# New_Project.net
KiCad netlist of a schematic drawn in EasyEDA Pro
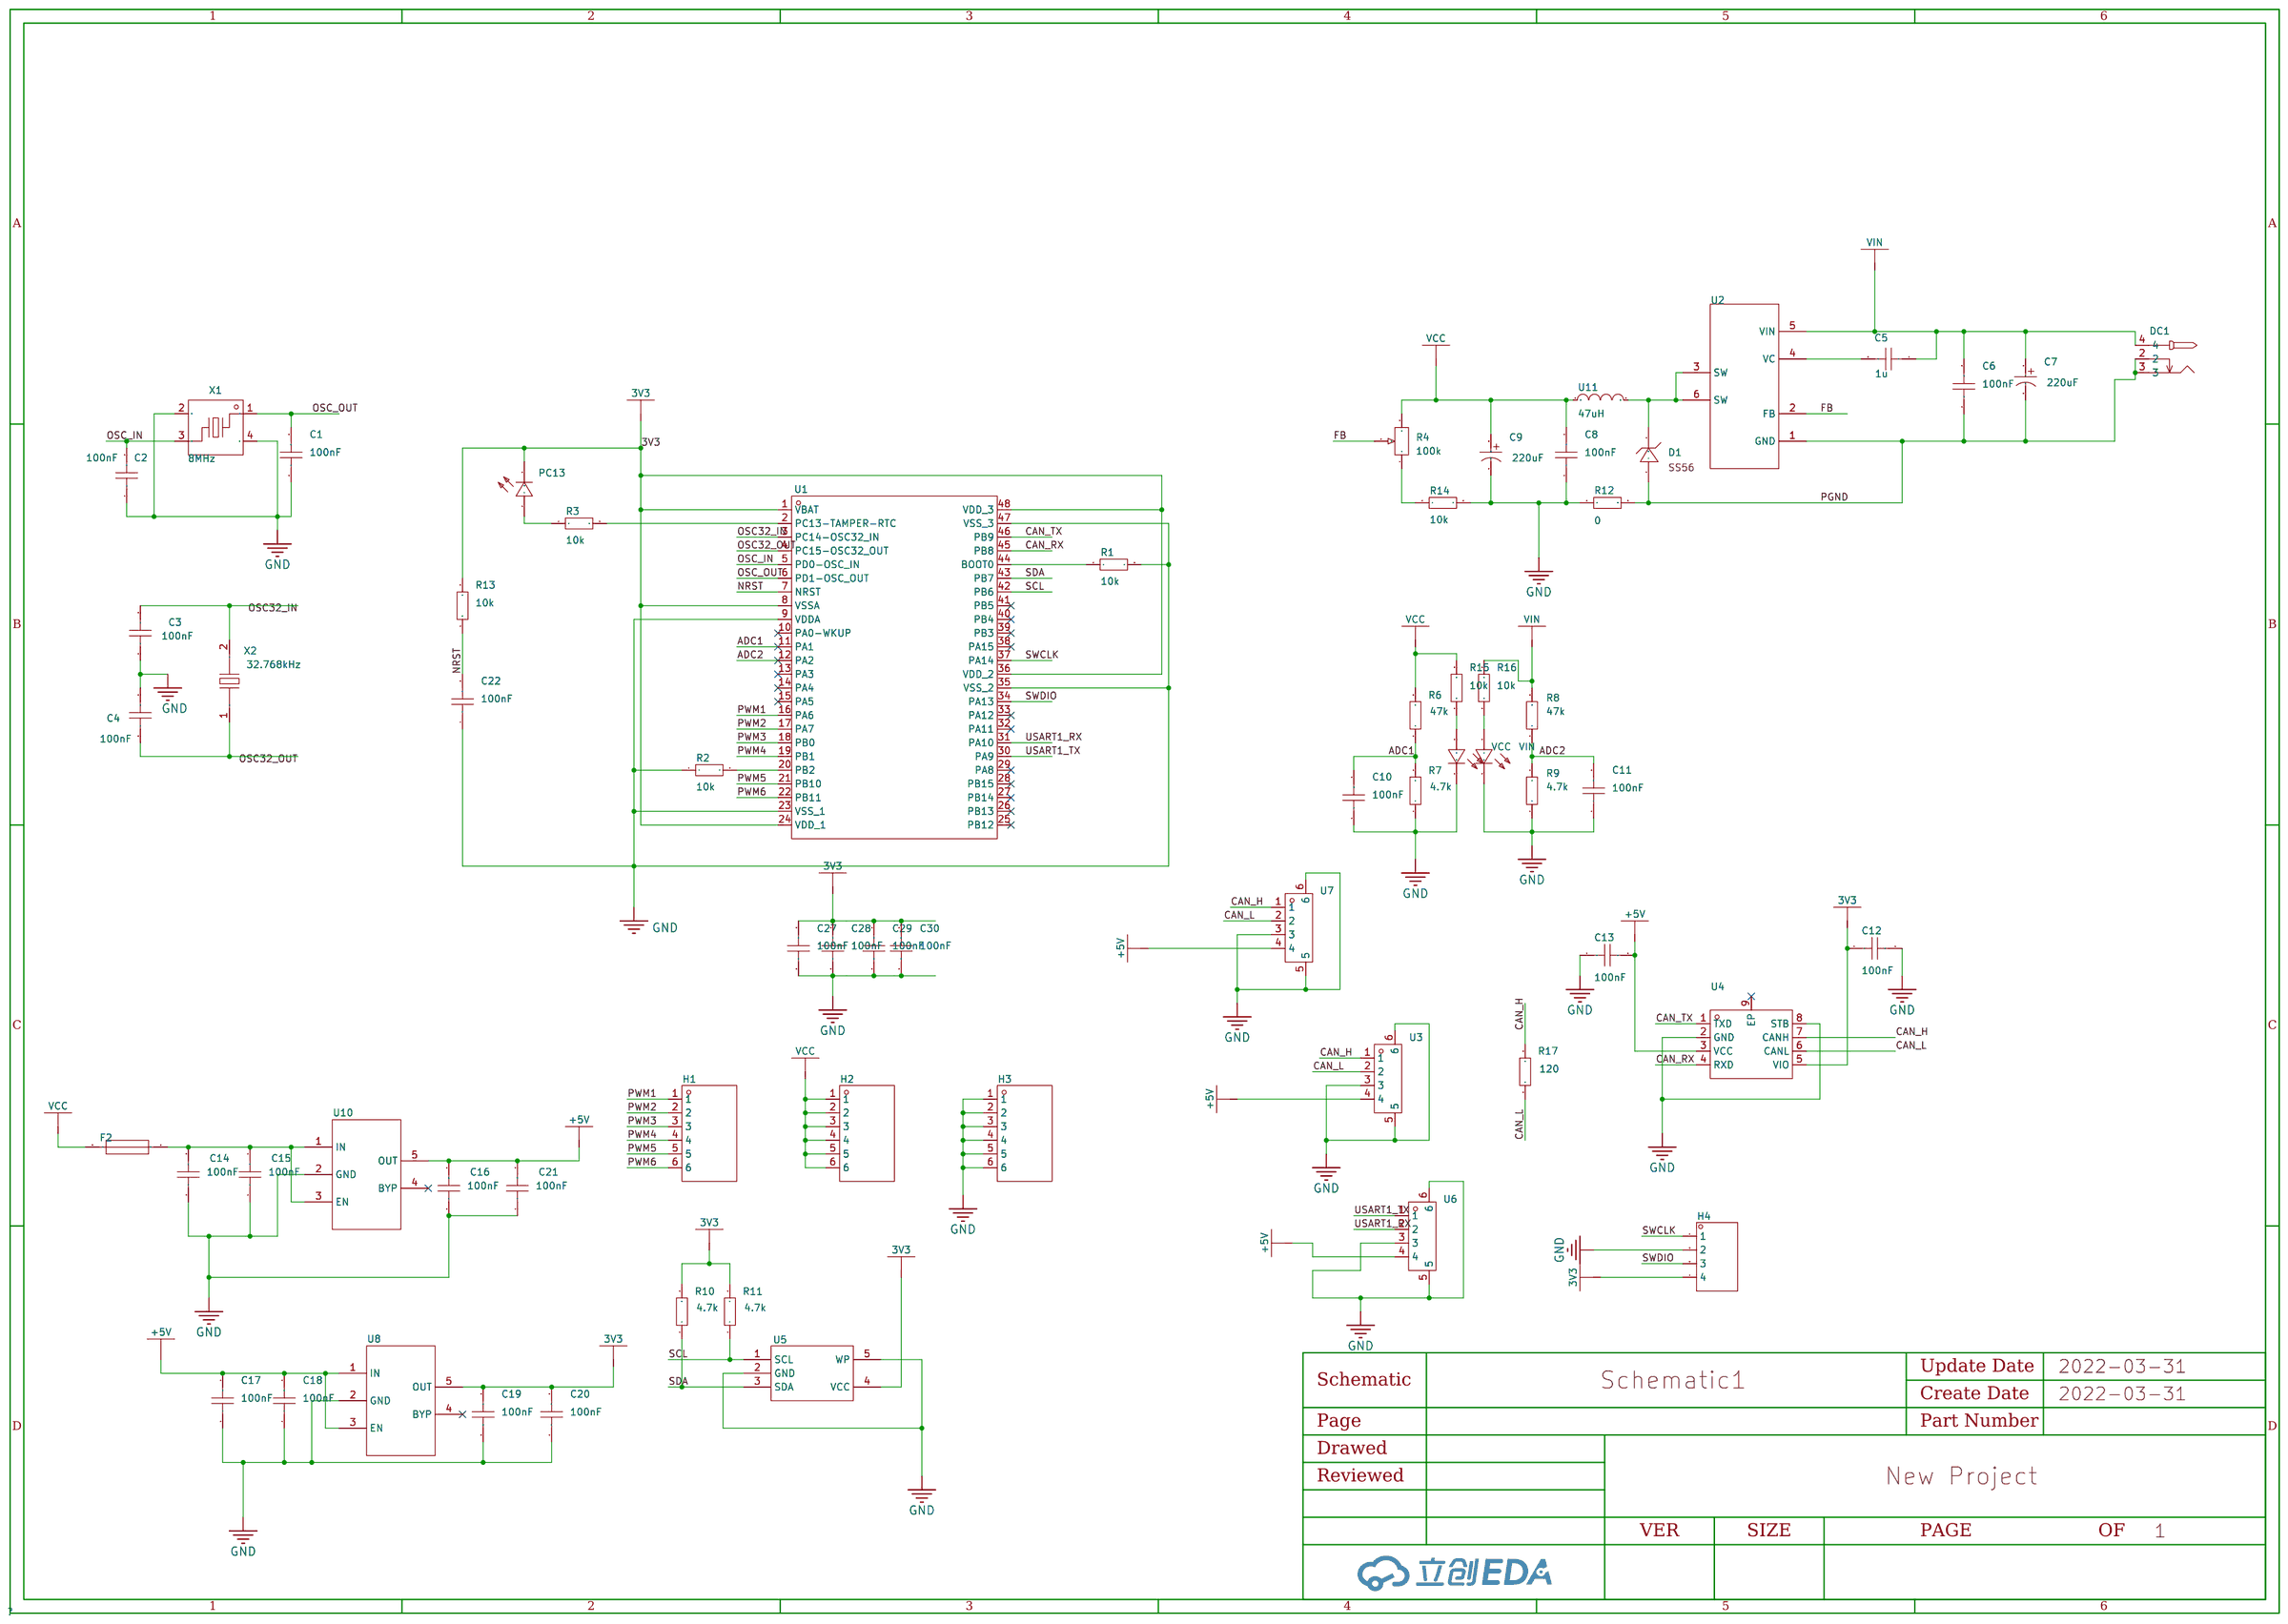
[diagram p0: schematic sheet]

(export (version "E")
  (design (tool "Eeschema 10.0.6"))
  (components
    (comp (ref "C1")
      (value "100nF")
      (footprint "easyedapro:C0603")
      (description "容值:100nF;精度:±10%;额定电压:50V;温度系数:X7R;")
      (fields
        (field (name "Manufacturer Part") "CC0603KRX7R9BB104")
        (field (name "Manufacturer") "YAGEO(国巨)")
      )
      (libsource (lib "easyedapro") (part "CC0603KRX7R9BB104"))
    )
    (comp (ref "C2")
      (value "100nF")
      (footprint "easyedapro:C0603")
      (description "容值:100nF;精度:±10%;额定电压:50V;温度系数:X7R;")
      (fields
        (field (name "Manufacturer Part") "CC0603KRX7R9BB104")
        (field (name "Manufacturer") "YAGEO(国巨)")
      )
      (libsource (lib "easyedapro") (part "CC0603KRX7R9BB104"))
    )
    (comp (ref "C3")
      (value "100nF")
      (footprint "easyedapro:C0603")
      (description "容值:100nF;精度:±10%;额定电压:50V;温度系数:X7R;")
      (fields
        (field (name "Manufacturer Part") "CC0603KRX7R9BB104")
        (field (name "Manufacturer") "YAGEO(国巨)")
      )
      (libsource (lib "easyedapro") (part "CC0603KRX7R9BB104"))
    )
    (comp (ref "C4")
      (value "100nF")
      (footprint "easyedapro:C0603")
      (description "容值:100nF;精度:±10%;额定电压:50V;温度系数:X7R;")
      (fields
        (field (name "Manufacturer Part") "CC0603KRX7R9BB104")
        (field (name "Manufacturer") "YAGEO(国巨)")
      )
      (libsource (lib "easyedapro") (part "CC0603KRX7R9BB104"))
    )
    (comp (ref "C5")
      (value "1u")
      (footprint "easyedapro:C0603")
      (description "容值:100nF;精度:±10%;额定电压:50V;温度系数:X7R;")
      (fields
        (field (name "Manufacturer Part") "CC0603KRX7R9BB104")
        (field (name "Manufacturer") "YAGEO(国巨)")
      )
      (libsource (lib "easyedapro") (part "CC0603KRX7R9BB104"))
    )
    (comp (ref "C6")
      (value "100nF")
      (footprint "easyedapro:C0603")
      (description "容值:100nF;精度:±10%;额定电压:50V;温度系数:X7R;")
      (fields
        (field (name "Manufacturer Part") "CC0603KRX7R9BB104")
        (field (name "Manufacturer") "YAGEO(国巨)")
      )
      (libsource (lib "easyedapro") (part "CC0603KRX7R9BB104"))
    )
    (comp (ref "C7")
      (value "220uF")
      (footprint "easyedapro:CAP-SMD_BD6.3-L6.6-W6.6-FD-1")
      (description "容值:10uF;精度:±20%;额定电压:50V;电容体直径:6.3mm;电容体长度:5.5mm;纹波电流:-;等效串联电阻:-;工作寿命:2000hrs@85;工作温度:-40~+85;")
      (fields
        (field (name "Manufacturer Part") "50SEV10M6.3X5.5")
        (field (name "Manufacturer") "rubycon(红宝石)")
      )
      (libsource (lib "easyedapro") (part "50SEV10M6.3X5.5"))
    )
    (comp (ref "C8")
      (value "100nF")
      (footprint "easyedapro:C0603")
      (description "容值:100nF;精度:±10%;额定电压:50V;温度系数:X7R;")
      (fields
        (field (name "Manufacturer Part") "CC0603KRX7R9BB104")
        (field (name "Manufacturer") "YAGEO(国巨)")
      )
      (libsource (lib "easyedapro") (part "CC0603KRX7R9BB104"))
    )
    (comp (ref "C9")
      (value "220uF")
      (footprint "easyedapro:CAP-SMD_BD6.3-L6.6-W6.6-FD-1")
      (description "容值:10uF;精度:±20%;额定电压:50V;电容体直径:6.3mm;电容体长度:5.5mm;纹波电流:-;等效串联电阻:-;工作寿命:2000hrs@85;工作温度:-40~+85;")
      (fields
        (field (name "Manufacturer Part") "50SEV10M6.3X5.5")
        (field (name "Manufacturer") "rubycon(红宝石)")
      )
      (libsource (lib "easyedapro") (part "50SEV10M6.3X5.5"))
    )
    (comp (ref "C10")
      (value "100nF")
      (footprint "easyedapro:C0603")
      (description "容值:100nF;精度:±10%;额定电压:50V;温度系数:X7R;")
      (fields
        (field (name "Manufacturer Part") "CC0603KRX7R9BB104")
        (field (name "Manufacturer") "YAGEO(国巨)")
      )
      (libsource (lib "easyedapro") (part "CC0603KRX7R9BB104"))
    )
    (comp (ref "C11")
      (value "100nF")
      (footprint "easyedapro:C0603")
      (description "容值:100nF;精度:±10%;额定电压:50V;温度系数:X7R;")
      (fields
        (field (name "Manufacturer Part") "CC0603KRX7R9BB104")
        (field (name "Manufacturer") "YAGEO(国巨)")
      )
      (libsource (lib "easyedapro") (part "CC0603KRX7R9BB104"))
    )
    (comp (ref "C12")
      (value "100nF")
      (footprint "easyedapro:C0603")
      (description "容值:100nF;精度:±10%;额定电压:50V;温度系数:X7R;")
      (fields
        (field (name "Manufacturer Part") "CC0603KRX7R9BB104")
        (field (name "Manufacturer") "YAGEO(国巨)")
      )
      (libsource (lib "easyedapro") (part "CC0603KRX7R9BB104"))
    )
    (comp (ref "C13")
      (value "100nF")
      (footprint "easyedapro:C0603")
      (description "容值:100nF;精度:±10%;额定电压:50V;温度系数:X7R;")
      (fields
        (field (name "Manufacturer Part") "CC0603KRX7R9BB104")
        (field (name "Manufacturer") "YAGEO(国巨)")
      )
      (libsource (lib "easyedapro") (part "CC0603KRX7R9BB104"))
    )
    (comp (ref "C14")
      (value "100nF")
      (footprint "easyedapro:C0603")
      (description "容值:100nF;精度:±10%;额定电压:50V;温度系数:X7R;")
      (fields
        (field (name "Manufacturer Part") "CC0603KRX7R9BB104")
        (field (name "Manufacturer") "YAGEO(国巨)")
      )
      (libsource (lib "easyedapro") (part "CC0603KRX7R9BB104"))
    )
    (comp (ref "C15")
      (value "100nF")
      (footprint "easyedapro:C0603")
      (description "容值:100nF;精度:±10%;额定电压:50V;温度系数:X7R;")
      (fields
        (field (name "Manufacturer Part") "CC0603KRX7R9BB104")
        (field (name "Manufacturer") "YAGEO(国巨)")
      )
      (libsource (lib "easyedapro") (part "CC0603KRX7R9BB104"))
    )
    (comp (ref "C16")
      (value "100nF")
      (footprint "easyedapro:C0603")
      (description "容值:100nF;精度:±10%;额定电压:50V;温度系数:X7R;")
      (fields
        (field (name "Manufacturer Part") "CC0603KRX7R9BB104")
        (field (name "Manufacturer") "YAGEO(国巨)")
      )
      (libsource (lib "easyedapro") (part "CC0603KRX7R9BB104"))
    )
    (comp (ref "C17")
      (value "100nF")
      (footprint "easyedapro:C0603")
      (description "容值:100nF;精度:±10%;额定电压:50V;温度系数:X7R;")
      (fields
        (field (name "Manufacturer Part") "CC0603KRX7R9BB104")
        (field (name "Manufacturer") "YAGEO(国巨)")
      )
      (libsource (lib "easyedapro") (part "CC0603KRX7R9BB104"))
    )
    (comp (ref "C18")
      (value "100nF")
      (footprint "easyedapro:C0603")
      (description "容值:100nF;精度:±10%;额定电压:50V;温度系数:X7R;")
      (fields
        (field (name "Manufacturer Part") "CC0603KRX7R9BB104")
        (field (name "Manufacturer") "YAGEO(国巨)")
      )
      (libsource (lib "easyedapro") (part "CC0603KRX7R9BB104"))
    )
    (comp (ref "C19")
      (value "100nF")
      (footprint "easyedapro:C0603")
      (description "容值:100nF;精度:±10%;额定电压:50V;温度系数:X7R;")
      (fields
        (field (name "Manufacturer Part") "CC0603KRX7R9BB104")
        (field (name "Manufacturer") "YAGEO(国巨)")
      )
      (libsource (lib "easyedapro") (part "CC0603KRX7R9BB104"))
    )
    (comp (ref "C20")
      (value "100nF")
      (footprint "easyedapro:C0603")
      (description "容值:100nF;精度:±10%;额定电压:50V;温度系数:X7R;")
      (fields
        (field (name "Manufacturer Part") "CC0603KRX7R9BB104")
        (field (name "Manufacturer") "YAGEO(国巨)")
      )
      (libsource (lib "easyedapro") (part "CC0603KRX7R9BB104"))
    )
    (comp (ref "C21")
      (value "100nF")
      (footprint "easyedapro:C0603")
      (description "容值:100nF;精度:±10%;额定电压:50V;温度系数:X7R;")
      (fields
        (field (name "Manufacturer Part") "CC0603KRX7R9BB104")
        (field (name "Manufacturer") "YAGEO(国巨)")
      )
      (libsource (lib "easyedapro") (part "CC0603KRX7R9BB104"))
    )
    (comp (ref "C22")
      (value "100nF")
      (footprint "easyedapro:C0603")
      (description "容值:100nF;精度:±10%;额定电压:50V;温度系数:X7R;")
      (fields
        (field (name "Manufacturer Part") "CC0603KRX7R9BB104")
        (field (name "Manufacturer") "YAGEO(国巨)")
      )
      (libsource (lib "easyedapro") (part "CC0603KRX7R9BB104"))
    )
    (comp (ref "C27")
      (value "100nF")
      (footprint "easyedapro:C0603")
      (description "容值:100nF;精度:±10%;额定电压:50V;温度系数:X7R;")
      (fields
        (field (name "Manufacturer Part") "CC0603KRX7R9BB104")
        (field (name "Manufacturer") "YAGEO(国巨)")
      )
      (libsource (lib "easyedapro") (part "CC0603KRX7R9BB104"))
    )
    (comp (ref "C28")
      (value "100nF")
      (footprint "easyedapro:C0603")
      (description "容值:100nF;精度:±10%;额定电压:50V;温度系数:X7R;")
      (fields
        (field (name "Manufacturer Part") "CC0603KRX7R9BB104")
        (field (name "Manufacturer") "YAGEO(国巨)")
      )
      (libsource (lib "easyedapro") (part "CC0603KRX7R9BB104"))
    )
    (comp (ref "C29")
      (value "100nF")
      (footprint "easyedapro:C0603")
      (description "容值:100nF;精度:±10%;额定电压:50V;温度系数:X7R;")
      (fields
        (field (name "Manufacturer Part") "CC0603KRX7R9BB104")
        (field (name "Manufacturer") "YAGEO(国巨)")
      )
      (libsource (lib "easyedapro") (part "CC0603KRX7R9BB104"))
    )
    (comp (ref "C30")
      (value "100nF")
      (footprint "easyedapro:C0603")
      (description "容值:100nF;精度:±10%;额定电压:50V;温度系数:X7R;")
      (fields
        (field (name "Manufacturer Part") "CC0603KRX7R9BB104")
        (field (name "Manufacturer") "YAGEO(国巨)")
      )
      (libsource (lib "easyedapro") (part "CC0603KRX7R9BB104"))
    )
    (comp (ref "D1")
      (value "~")
      (footprint "easyedapro:SMA_L4.4-W2.6-LS5.0-RD")
      (description "直流反向耐压（Vr）:60V;平均整流电流（Io）:5A;正向压降（Vf）:550mV @ 5A;")
      (fields (field (name "Manufacturer Part") "SS56") (field (name "LCSC Part Name") "SS56"))
      (libsource (lib "easyedapro") (part "SS56_C379835"))
    )
    (comp (ref "DC1")
      (value "~")
      (footprint "easyedapro:DC-IN-TH_DC-5520-1")
      (description "连接器类型:DC电源插座;安装方式:弯插;触点内径:2mm;触点外径:6.4mm;额定电流:-;额定电压:-;工作温度范围:-;")
      (fields (field (name "Manufacturer Part") "DC-005 2.0") (field (name "Manufacturer") "BOOMELE(博穆精密)"))
      (libsource (lib "easyedapro") (part "DC-005 5.5-2.0MM"))
    )
    (comp (ref "F2")
      (value "~")
      (footprint "easyedapro:F1206")
      (fields (field (name "Manufacturer Part") "JK-nSMD050-30") (field (name "Manufacturer") "JK(金科)"))
      (libsource (lib "easyedapro") (part "JK-NSMD050-30V"))
    )
    (comp (ref "H1")
      (value "~")
      (footprint "easyedapro:HDR-TH_6P-P2.54-V_Z-211-0611-0021-001")
      (fields
        (field (name "Manufacturer Part") "Z-211-0611-0021-001")
        (field (name "Manufacturer") "Nextron(台湾正凌)")
      )
      (libsource (lib "easyedapro") (part "Z-211-0611-0021-001"))
    )
    (comp (ref "H2")
      (value "~")
      (footprint "easyedapro:HDR-TH_6P-P2.54-V_Z-211-0611-0021-001")
      (fields
        (field (name "Manufacturer Part") "Z-211-0611-0021-001")
        (field (name "Manufacturer") "Nextron(台湾正凌)")
      )
      (libsource (lib "easyedapro") (part "Z-211-0611-0021-001"))
    )
    (comp (ref "H3")
      (value "~")
      (footprint "easyedapro:HDR-TH_6P-P2.54-V_Z-211-0611-0021-001")
      (fields
        (field (name "Manufacturer Part") "Z-211-0611-0021-001")
        (field (name "Manufacturer") "Nextron(台湾正凌)")
      )
      (libsource (lib "easyedapro") (part "Z-211-0611-0021-001"))
    )
    (comp (ref "H4")
      (value "~")
      (footprint "easyedapro:HDR-TH_4P-P2.54-V-M")
      (fields (field (name "Manufacturer Part") "B-2100S04P-A110") (field (name "Manufacturer") "Ckmtw(灿科盟)"))
      (libsource (lib "easyedapro") (part "Header-Male-2.54_1x4"))
    )
    (comp (ref "PC13")
      (value "~")
      (footprint "easyedapro:LED0603-R-RD")
      (fields
        (field (name "Manufacturer Part") "19-217/GHC-YR1S2/3T")
        (field (name "Manufacturer") "EVERLIGHT(台湾亿光)")
      )
      (libsource (lib "easyedapro") (part "19-217/GHC-YR1S2/3T"))
    )
    (comp (ref "R1")
      (value "10k")
      (footprint "easyedapro:R0201")
      (description "阻值:10k;精度:±1%;功率:50mW;温度系数:±200ppm/;最大工作电压:25V;工作温度范围:-55~+125;")
      (fields (field (name "Manufacturer Part") "RC-01W1002FT") (field (name "Manufacturer") "FH(风华)"))
      (libsource (lib "easyedapro") (part "RC-01W1002FT"))
    )
    (comp (ref "R2")
      (value "10k")
      (footprint "easyedapro:R0201")
      (description "阻值:10k;精度:±1%;功率:50mW;温度系数:±200ppm/;最大工作电压:25V;工作温度范围:-55~+125;")
      (fields (field (name "Manufacturer Part") "RC-01W1002FT") (field (name "Manufacturer") "FH(风华)"))
      (libsource (lib "easyedapro") (part "RC-01W1002FT"))
    )
    (comp (ref "R3")
      (value "10k")
      (footprint "easyedapro:R0201")
      (description "阻值:10k;精度:±1%;功率:50mW;温度系数:±200ppm/;最大工作电压:25V;工作温度范围:-55~+125;")
      (fields (field (name "Manufacturer Part") "RC-01W1002FT") (field (name "Manufacturer") "FH(风华)"))
      (libsource (lib "easyedapro") (part "RC-01W1002FT"))
    )
    (comp (ref "R4")
      (value "100k")
      (footprint "easyedapro:RES-ADJ-TH_3P-L9.5-W4.9-P2.50-L_3296W")
      (description "阻值:100k;精度:±10%;温度系数:±250ppm/;")
      (fields (field (name "Manufacturer Part") "3296W-1-104") (field (name "Manufacturer") "BOCHEN(博晨)"))
      (libsource (lib "easyedapro") (part "3296W-1-104"))
    )
    (comp (ref "R6")
      (value "47k")
      (footprint "easyedapro:R0201")
      (description "阻值:10k;精度:±1%;功率:50mW;温度系数:±200ppm/;最大工作电压:25V;工作温度范围:-55~+125;")
      (fields (field (name "Manufacturer Part") "RC-01W1002FT") (field (name "Manufacturer") "FH(风华)"))
      (libsource (lib "easyedapro") (part "RC-01W1002FT"))
    )
    (comp (ref "R7")
      (value "4.7k")
      (footprint "easyedapro:R0201")
      (description "阻值:10k;精度:±1%;功率:50mW;温度系数:±200ppm/;最大工作电压:25V;工作温度范围:-55~+125;")
      (fields (field (name "Manufacturer Part") "RC-01W1002FT") (field (name "Manufacturer") "FH(风华)"))
      (libsource (lib "easyedapro") (part "RC-01W1002FT"))
    )
    (comp (ref "R8")
      (value "47k")
      (footprint "easyedapro:R0201")
      (description "阻值:10k;精度:±1%;功率:50mW;温度系数:±200ppm/;最大工作电压:25V;工作温度范围:-55~+125;")
      (fields (field (name "Manufacturer Part") "RC-01W1002FT") (field (name "Manufacturer") "FH(风华)"))
      (libsource (lib "easyedapro") (part "RC-01W1002FT"))
    )
    (comp (ref "R9")
      (value "4.7k")
      (footprint "easyedapro:R0201")
      (description "阻值:10k;精度:±1%;功率:50mW;温度系数:±200ppm/;最大工作电压:25V;工作温度范围:-55~+125;")
      (fields (field (name "Manufacturer Part") "RC-01W1002FT") (field (name "Manufacturer") "FH(风华)"))
      (libsource (lib "easyedapro") (part "RC-01W1002FT"))
    )
    (comp (ref "R10")
      (value "4.7k")
      (footprint "easyedapro:R0603")
      (description "电阻类型:薄膜电阻;阻值:10k;精度:±0.1%;功率:100mW;温度系数:±25ppm/;最大工作电压:75V;工作温度范围:-55~+155;")
      (fields
        (field (name "Manufacturer Part") "TR0603B10K0P0525Z")
        (field (name "Manufacturer") "EVER OHMS(天二科技)")
      )
      (libsource (lib "easyedapro") (part "TR0603B10KP05250.1W"))
    )
    (comp (ref "R11")
      (value "4.7k")
      (footprint "easyedapro:R0603")
      (description "电阻类型:薄膜电阻;阻值:10k;精度:±0.1%;功率:100mW;温度系数:±25ppm/;最大工作电压:75V;工作温度范围:-55~+155;")
      (fields
        (field (name "Manufacturer Part") "TR0603B10K0P0525Z")
        (field (name "Manufacturer") "EVER OHMS(天二科技)")
      )
      (libsource (lib "easyedapro") (part "TR0603B10KP05250.1W"))
    )
    (comp (ref "R12")
      (value "0")
      (footprint "easyedapro:R1206")
      (description "电阻类型:厚膜电阻;阻值:10k;精度:±1%;功率:500mW;温度系数:±100ppm/;最大工作电压:200V;工作温度范围:-55~+155;")
      (fields (field (name "Manufacturer Part") "AC1206FR-7W10KL") (field (name "Manufacturer") "YAGEO(国巨)"))
      (libsource (lib "easyedapro") (part "AC1206FR-7W10KL"))
    )
    (comp (ref "R13")
      (value "10k")
      (footprint "easyedapro:R0603")
      (description "电阻类型:薄膜电阻;阻值:10k;精度:±0.1%;功率:100mW;温度系数:±25ppm/;最大工作电压:75V;工作温度范围:-55~+155;")
      (fields
        (field (name "Manufacturer Part") "TR0603B10K0P0525Z")
        (field (name "Manufacturer") "EVER OHMS(天二科技)")
      )
      (libsource (lib "easyedapro") (part "TR0603B10KP05250.1W"))
    )
    (comp (ref "R14")
      (value "10k")
      (footprint "easyedapro:R0603")
      (description "电阻类型:薄膜电阻;阻值:10k;精度:±0.1%;功率:100mW;温度系数:±25ppm/;最大工作电压:75V;工作温度范围:-55~+155;")
      (fields
        (field (name "Manufacturer Part") "TR0603B10K0P0525Z")
        (field (name "Manufacturer") "EVER OHMS(天二科技)")
      )
      (libsource (lib "easyedapro") (part "TR0603B10KP05250.1W"))
    )
    (comp (ref "R15")
      (value "10k")
      (footprint "easyedapro:R0603")
      (description "电阻类型:薄膜电阻;阻值:10k;精度:±0.1%;功率:100mW;温度系数:±25ppm/;最大工作电压:75V;工作温度范围:-55~+155;")
      (fields
        (field (name "Manufacturer Part") "TR0603B10K0P0525Z")
        (field (name "Manufacturer") "EVER OHMS(天二科技)")
      )
      (libsource (lib "easyedapro") (part "TR0603B10KP05250.1W"))
    )
    (comp (ref "R16")
      (value "10k")
      (footprint "easyedapro:R0603")
      (description "电阻类型:薄膜电阻;阻值:10k;精度:±0.1%;功率:100mW;温度系数:±25ppm/;最大工作电压:75V;工作温度范围:-55~+155;")
      (fields
        (field (name "Manufacturer Part") "TR0603B10K0P0525Z")
        (field (name "Manufacturer") "EVER OHMS(天二科技)")
      )
      (libsource (lib "easyedapro") (part "TR0603B10KP05250.1W"))
    )
    (comp (ref "R17")
      (value "120")
      (footprint "easyedapro:R0603")
      (description "电阻类型:薄膜电阻;阻值:10k;精度:±0.1%;功率:100mW;温度系数:±25ppm/;最大工作电压:75V;工作温度范围:-55~+155;")
      (fields
        (field (name "Manufacturer Part") "TR0603B10K0P0525Z")
        (field (name "Manufacturer") "EVER OHMS(天二科技)")
      )
      (libsource (lib "easyedapro") (part "TR0603B10KP05250.1W"))
    )
    (comp (ref "U1")
      (value "~")
      (footprint "easyedapro:LQFP-48_L7.0-W7.0-P0.50-LS9.0-BL")
      (description "主频（MAX):72MHz;工作电压:2V ~ 3.6V;")
      (fields (field (name "Manufacturer Part") "STM32F103C8T6") (field (name "Manufacturer") "ST(意法半导体)"))
      (libsource (lib "easyedapro") (part "STM32F103C8T6"))
    )
    (comp (ref "U2")
      (value "~")
      (footprint "easyedapro:TO-263-5_L10.2-W8.9-P1.70-TL")
      (description "功能类型:降压型;同步整流:-;输出通道数:-;拓扑结构:-;输入电压:-;输出电流(最大值):-;开关频率:-;")
      (fields (field (name "Manufacturer Part") "XL4015E1") (field (name "Manufacturer") "XLSEMI(芯龙)"))
      (libsource (lib "easyedapro") (part "XL4015E1"))
    )
    (comp (ref "U3")
      (value "~")
      (footprint "easyedapro:CONN-SMD_4P-P2.50_XH2.50-4AB")
      (fields (field (name "Manufacturer Part") "XH2.5-4P-LS"))
      (libsource (lib "easyedapro") (part "XH2.5-4P-LS"))
    )
    (comp (ref "U4")
      (value "~")
      (footprint "easyedapro:HVSON-8_L3.0-W3.0-P0.65-BL-EP")
      (description "类型:-;协议类别:-;驱动器/接收器数:-;数据速率:-;")
      (fields (field (name "Manufacturer Part") "SIT1042TK/3") (field (name "Manufacturer") "SIT(芯力特)"))
      (libsource (lib "easyedapro") (part "SIT1042TK/3"))
    )
    (comp (ref "U5")
      (value "~")
      (footprint "easyedapro:SOT-23-5_L3.0-W1.7-P0.95-LS2.8-BR")
      (description "存储器容量:2Kb (256 x 8);存储器接口类型:I2C;工作电压:1.8V ~ 5.5V;")
      (fields (field (name "Manufacturer Part") "K24C02") (field (name "Manufacturer") "华虹宏力"))
      (libsource (lib "easyedapro") (part "K24C02"))
    )
    (comp (ref "U6")
      (value "~")
      (footprint "easyedapro:CONN-SMD_4P-P2.50_XH2.50-4AB")
      (fields (field (name "Manufacturer Part") "XH2.5-4P-LS"))
      (libsource (lib "easyedapro") (part "XH2.5-4P-LS"))
    )
    (comp (ref "U7")
      (value "~")
      (footprint "easyedapro:CONN-SMD_4P-P2.50_XH2.50-4AB")
      (fields (field (name "Manufacturer Part") "XH2.5-4P-LS"))
      (libsource (lib "easyedapro") (part "XH2.5-4P-LS"))
    )
    (comp (ref "U8")
      (value "~")
      (footprint "easyedapro:SOT-23-5_L3.0-W1.7-P0.95-LS2.8-TL")
      (description "输出类型:固定;输出极性:正;输出通道数:1;最大输入电压:16V;输出电压:5V;压差:700mV@(500mA);输出电流:500mA;电源纹波抑制比(PRSS):-;")
      (fields
        (field (name "Manufacturer Part") "SPX3819M5-L-5-0/TR")
        (field (name "Manufacturer") "MaxLinear")
      )
      (libsource (lib "easyedapro") (part "SPX3819M5-L-5-0/TR"))
    )
    (comp (ref "U10")
      (value "~")
      (footprint "easyedapro:SOT-23-5_L3.0-W1.7-P0.95-LS2.8-BR")
      (description "输出类型:固定;输出极性:正;输出通道数:1;最大输入电压:16V;输出电压:3.3V;压差:700mV@(500mA);输出电流:500mA;电源纹波抑制比(PRSS):70dB;")
      (fields
        (field (name "Manufacturer Part") "SPX3819M5-L-3-3/TR")
        (field (name "Manufacturer") "MaxLinear")
      )
      (libsource (lib "easyedapro") (part "SPX3819M5-L-3-3/TR"))
    )
    (comp (ref "U11")
      (value "47uH")
      (footprint "easyedapro:IND-TH_L12.5-W6.5-P8.00-D0.5")
      (description "类型:磁环电感;电感值:47uH;精度:±20%;额定电流:2A;饱和电流(Isat):-;直流电阻(DCR):42m;Q值:-;自谐频率:-;车规等级:-;脚间距:-;")
      (fields
        (field (name "Manufacturer Part") "SLT040125T470MUB")
        (field (name "Manufacturer") "Sunltech(韩国顺磁)")
      )
      (libsource (lib "easyedapro") (part "SLT040125T470MUB"))
    )
    (comp (ref "VCC")
      (value "~")
      (footprint "easyedapro:LED0603-R-RD")
      (fields
        (field (name "Manufacturer Part") "19-217/GHC-YR1S2/3T")
        (field (name "Manufacturer") "EVERLIGHT(台湾亿光)")
      )
      (libsource (lib "easyedapro") (part "19-217/GHC-YR1S2/3T"))
    )
    (comp (ref "VIN")
      (value "~")
      (footprint "easyedapro:LED0603-R-RD")
      (fields
        (field (name "Manufacturer Part") "19-217/GHC-YR1S2/3T")
        (field (name "Manufacturer") "EVERLIGHT(台湾亿光)")
      )
      (libsource (lib "easyedapro") (part "19-217/GHC-YR1S2/3T"))
    )
    (comp (ref "X1")
      (value "8MHz")
      (footprint "easyedapro:CRYSTAL-SMD_4P-L3.2-W2.5-BL")
      (description "晶振类型:贴片无源晶振;频率:8MHz;频率公差:±10ppm;频率稳定度:±30ppm;负载电容:20pF;工作温度:-40~+85;")
      (fields (field (name "Manufacturer Part") "X32258MSB4SI") (field (name "Manufacturer") "YXC扬兴科技"))
      (libsource (lib "easyedapro") (part "X32258MSB4SI"))
    )
    (comp (ref "X2")
      (value "32.768kHz")
      (footprint "easyedapro:OSC-SMD_2P-L3.2-W1.5-1")
      (description "晶振类型:贴片无源晶振;频率:32.768kHz;频率公差:±20ppm;频率稳定度:-;负载电容:7pF;等效串联电阻(ESR):70k;工作温度:-40~+85;")
      (fields (field (name "Manufacturer Part") "G3100327072070CY") (field (name "Manufacturer") "JGHC(晶光华)"))
      (libsource (lib "easyedapro") (part "G3100327072070CY"))
    )
  )
  (nets
    (net (code "1") (name "+5V") (class "Default")
      (node (ref "C13") (pin "2") (pinfunction "2_2") (pintype "input"))
      (node (ref "C16") (pin "2") (pinfunction "2_2") (pintype "input"))
      (node (ref "C17") (pin "2") (pinfunction "2_2") (pintype "input"))
      (node (ref "C18") (pin "2") (pinfunction "2_2") (pintype "input"))
      (node (ref "C21") (pin "2") (pinfunction "2_2") (pintype "input"))
      (node (ref "U10") (pin "5") (pinfunction "OUT_5") (pintype "input"))
      (node (ref "U3") (pin "4") (pinfunction "4_4") (pintype "input"))
      (node (ref "U4") (pin "3") (pinfunction "VCC_3") (pintype "input"))
      (node (ref "U6") (pin "4") (pinfunction "4_4") (pintype "input"))
      (node (ref "U7") (pin "4") (pinfunction "4_4") (pintype "input"))
      (node (ref "U8") (pin "1") (pinfunction "IN_1") (pintype "input"))
      (node (ref "U8") (pin "3") (pinfunction "EN_3") (pintype "input"))
    )
    (net (code "2") (name "/ADC1") (class "Default")
      (node (ref "C10") (pin "2") (pinfunction "2_2") (pintype "input"))
      (node (ref "R6") (pin "1") (pinfunction "1_1") (pintype "input"))
      (node (ref "R7") (pin "2") (pinfunction "2_2") (pintype "input"))
      (node (ref "U1") (pin "11") (pinfunction "PA1_11") (pintype "input"))
    )
    (net (code "3") (name "/ADC2") (class "Default")
      (node (ref "C11") (pin "2") (pinfunction "2_2") (pintype "input"))
      (node (ref "R8") (pin "1") (pinfunction "1_1") (pintype "input"))
      (node (ref "R9") (pin "2") (pinfunction "2_2") (pintype "input"))
      (node (ref "U1") (pin "12") (pinfunction "PA2_12") (pintype "input"))
    )
    (net (code "4") (name "/CAN_H") (class "Default")
      (node (ref "R17") (pin "2") (pinfunction "2_2") (pintype "input"))
      (node (ref "U3") (pin "1") (pinfunction "1_1") (pintype "input"))
      (node (ref "U4") (pin "7") (pinfunction "CANH_7") (pintype "input"))
      (node (ref "U7") (pin "1") (pinfunction "1_1") (pintype "input"))
    )
    (net (code "5") (name "/CAN_L") (class "Default")
      (node (ref "R17") (pin "1") (pinfunction "1_1") (pintype "input"))
      (node (ref "U3") (pin "2") (pinfunction "2_2") (pintype "input"))
      (node (ref "U4") (pin "6") (pinfunction "CANL_6") (pintype "input"))
      (node (ref "U7") (pin "2") (pinfunction "2_2") (pintype "input"))
    )
    (net (code "6") (name "/CAN_RX") (class "Default")
      (node (ref "U1") (pin "45") (pinfunction "PB8_45") (pintype "input"))
      (node (ref "U4") (pin "4") (pinfunction "RXD_4") (pintype "input"))
    )
    (net (code "7") (name "/CAN_TX") (class "Default")
      (node (ref "U1") (pin "46") (pinfunction "PB9_46") (pintype "input"))
      (node (ref "U4") (pin "1") (pinfunction "TXD_1") (pintype "input"))
    )
    (net (code "8") (name "/FB") (class "Default")
      (node (ref "R4") (pin "2") (pinfunction "2_2") (pintype "input"))
      (node (ref "U2") (pin "2") (pinfunction "FB_2") (pintype "input"))
    )
    (net (code "9") (name "/NRST") (class "Default")
      (node (ref "C22") (pin "2") (pinfunction "2_2") (pintype "input"))
      (node (ref "R13") (pin "1") (pinfunction "1_1") (pintype "input"))
      (node (ref "U1") (pin "7") (pinfunction "NRST_7") (pintype "input"))
    )
    (net (code "10") (name "/OSC32_IN") (class "Default")
      (node (ref "C3") (pin "2") (pinfunction "2_2") (pintype "input"))
      (node (ref "U1") (pin "3") (pinfunction "PC14-OSC32_IN_3") (pintype "input"))
      (node (ref "X2") (pin "2") (pinfunction "2_2") (pintype "input"))
    )
    (net (code "11") (name "/OSC32_OUT") (class "Default")
      (node (ref "C4") (pin "2") (pinfunction "2_2") (pintype "input"))
      (node (ref "U1") (pin "4") (pinfunction "PC15-OSC32_OUT_4") (pintype "input"))
      (node (ref "X2") (pin "1") (pinfunction "1_1") (pintype "input"))
    )
    (net (code "12") (name "/OSC_IN") (class "Default")
      (node (ref "C2") (pin "2") (pinfunction "2_2") (pintype "input"))
      (node (ref "U1") (pin "5") (pinfunction "PD0-OSC_IN_5") (pintype "input"))
      (node (ref "X1") (pin "3") (pinfunction "3_3") (pintype "input"))
    )
    (net (code "13") (name "/OSC_OUT") (class "Default")
      (node (ref "C1") (pin "2") (pinfunction "2_2") (pintype "input"))
      (node (ref "U1") (pin "6") (pinfunction "PD1-OSC_OUT_6") (pintype "input"))
      (node (ref "X1") (pin "1") (pinfunction "1_1") (pintype "input"))
    )
    (net (code "14") (name "/PGND") (class "Default")
      (node (ref "C6") (pin "1") (pinfunction "1_1") (pintype "input"))
      (node (ref "C7") (pin "2") (pinfunction "2_2") (pintype "input"))
      (node (ref "D1") (pin "2") (pinfunction "A_2") (pintype "input"))
      (node (ref "DC1") (pin "2") (pinfunction "2_2") (pintype "input"))
      (node (ref "DC1") (pin "3") (pinfunction "3_3") (pintype "input"))
      (node (ref "R12") (pin "2") (pinfunction "2_2") (pintype "input"))
      (node (ref "U2") (pin "1") (pinfunction "GND_1") (pintype "input"))
    )
    (net (code "15") (name "/PWM1") (class "Default")
      (node (ref "H1") (pin "1") (pinfunction "1_1") (pintype "input"))
      (node (ref "U1") (pin "16") (pinfunction "PA6_16") (pintype "input"))
    )
    (net (code "16") (name "/PWM2") (class "Default")
      (node (ref "H1") (pin "2") (pinfunction "2_2") (pintype "input"))
      (node (ref "U1") (pin "17") (pinfunction "PA7_17") (pintype "input"))
    )
    (net (code "17") (name "/PWM3") (class "Default")
      (node (ref "H1") (pin "3") (pinfunction "3_3") (pintype "input"))
      (node (ref "U1") (pin "18") (pinfunction "PB0_18") (pintype "input"))
    )
    (net (code "18") (name "/PWM4") (class "Default")
      (node (ref "H1") (pin "4") (pinfunction "4_4") (pintype "input"))
      (node (ref "U1") (pin "19") (pinfunction "PB1_19") (pintype "input"))
    )
    (net (code "19") (name "/PWM5") (class "Default")
      (node (ref "H1") (pin "5") (pinfunction "5_5") (pintype "input"))
      (node (ref "U1") (pin "21") (pinfunction "PB10_21") (pintype "input"))
    )
    (net (code "20") (name "/PWM6") (class "Default")
      (node (ref "H1") (pin "6") (pinfunction "6_6") (pintype "input"))
      (node (ref "U1") (pin "22") (pinfunction "PB11_22") (pintype "input"))
    )
    (net (code "21") (name "/SCL") (class "Default")
      (node (ref "R11") (pin "1") (pinfunction "1_1") (pintype "input"))
      (node (ref "U1") (pin "42") (pinfunction "PB6_42") (pintype "input"))
      (node (ref "U5") (pin "1") (pinfunction "SCL_1") (pintype "input"))
    )
    (net (code "22") (name "/SDA") (class "Default")
      (node (ref "R10") (pin "1") (pinfunction "1_1") (pintype "input"))
      (node (ref "U1") (pin "43") (pinfunction "PB7_43") (pintype "input"))
      (node (ref "U5") (pin "3") (pinfunction "SDA_3") (pintype "input"))
    )
    (net (code "23") (name "/SWCLK") (class "Default")
      (node (ref "H4") (pin "1") (pinfunction "1_1") (pintype "input"))
      (node (ref "U1") (pin "37") (pinfunction "PA14_37") (pintype "input"))
    )
    (net (code "24") (name "/SWDIO") (class "Default")
      (node (ref "H4") (pin "3") (pinfunction "3_3") (pintype "input"))
      (node (ref "U1") (pin "34") (pinfunction "PA13_34") (pintype "input"))
    )
    (net (code "25") (name "/USART1_RX") (class "Default")
      (node (ref "U1") (pin "31") (pinfunction "PA10_31") (pintype "input"))
      (node (ref "U6") (pin "2") (pinfunction "2_2") (pintype "input"))
    )
    (net (code "26") (name "/USART1_TX") (class "Default")
      (node (ref "U1") (pin "30") (pinfunction "PA9_30") (pintype "input"))
      (node (ref "U6") (pin "1") (pinfunction "1_1") (pintype "input"))
    )
    (net (code "27") (name "3V3") (class "Default")
      (node (ref "C12") (pin "1") (pinfunction "1_1") (pintype "input"))
      (node (ref "C19") (pin "2") (pinfunction "2_2") (pintype "input"))
      (node (ref "C20") (pin "2") (pinfunction "2_2") (pintype "input"))
      (node (ref "C27") (pin "2") (pinfunction "2_2") (pintype "input"))
      (node (ref "C28") (pin "2") (pinfunction "2_2") (pintype "input"))
      (node (ref "C29") (pin "2") (pinfunction "2_2") (pintype "input"))
      (node (ref "C30") (pin "2") (pinfunction "2_2") (pintype "input"))
      (node (ref "H4") (pin "4") (pinfunction "4_4") (pintype "input"))
      (node (ref "PC13") (pin "2") (pinfunction "C_2") (pintype "input"))
      (node (ref "R10") (pin "2") (pinfunction "2_2") (pintype "input"))
      (node (ref "R11") (pin "2") (pinfunction "2_2") (pintype "input"))
      (node (ref "R13") (pin "2") (pinfunction "2_2") (pintype "input"))
      (node (ref "U1") (pin "1") (pinfunction "VBAT_1") (pintype "input"))
      (node (ref "U1") (pin "24") (pinfunction "VDD_1_24") (pintype "input"))
      (node (ref "U1") (pin "36") (pinfunction "VDD_2_36") (pintype "input"))
      (node (ref "U1") (pin "48") (pinfunction "VDD_3_48") (pintype "input"))
      (node (ref "U1") (pin "8") (pinfunction "VSSA_8") (pintype "input"))
      (node (ref "U4") (pin "5") (pinfunction "VIO_5") (pintype "input"))
      (node (ref "U5") (pin "4") (pinfunction "VCC_4") (pintype "input"))
      (node (ref "U8") (pin "5") (pinfunction "OUT_5") (pintype "input"))
    )
    (net (code "28") (name "GND") (class "Default")
      (node (ref "C1") (pin "1") (pinfunction "1_1") (pintype "input"))
      (node (ref "C10") (pin "1") (pinfunction "1_1") (pintype "input"))
      (node (ref "C11") (pin "1") (pinfunction "1_1") (pintype "input"))
      (node (ref "C12") (pin "2") (pinfunction "2_2") (pintype "input"))
      (node (ref "C13") (pin "1") (pinfunction "1_1") (pintype "input"))
      (node (ref "C14") (pin "1") (pinfunction "1_1") (pintype "input"))
      (node (ref "C15") (pin "1") (pinfunction "1_1") (pintype "input"))
      (node (ref "C16") (pin "1") (pinfunction "1_1") (pintype "input"))
      (node (ref "C17") (pin "1") (pinfunction "1_1") (pintype "input"))
      (node (ref "C18") (pin "1") (pinfunction "1_1") (pintype "input"))
      (node (ref "C19") (pin "1") (pinfunction "1_1") (pintype "input"))
      (node (ref "C2") (pin "1") (pinfunction "1_1") (pintype "input"))
      (node (ref "C20") (pin "1") (pinfunction "1_1") (pintype "input"))
      (node (ref "C21") (pin "1") (pinfunction "1_1") (pintype "input"))
      (node (ref "C22") (pin "1") (pinfunction "1_1") (pintype "input"))
      (node (ref "C27") (pin "1") (pinfunction "1_1") (pintype "input"))
      (node (ref "C28") (pin "1") (pinfunction "1_1") (pintype "input"))
      (node (ref "C29") (pin "1") (pinfunction "1_1") (pintype "input"))
      (node (ref "C3") (pin "1") (pinfunction "1_1") (pintype "input"))
      (node (ref "C30") (pin "1") (pinfunction "1_1") (pintype "input"))
      (node (ref "C4") (pin "1") (pinfunction "1_1") (pintype "input"))
      (node (ref "C8") (pin "1") (pinfunction "1_1") (pintype "input"))
      (node (ref "C9") (pin "2") (pinfunction "2_2") (pintype "input"))
      (node (ref "H3") (pin "1") (pinfunction "1_1") (pintype "input"))
      (node (ref "H3") (pin "2") (pinfunction "2_2") (pintype "input"))
      (node (ref "H3") (pin "3") (pinfunction "3_3") (pintype "input"))
      (node (ref "H3") (pin "4") (pinfunction "4_4") (pintype "input"))
      (node (ref "H3") (pin "5") (pinfunction "5_5") (pintype "input"))
      (node (ref "H3") (pin "6") (pinfunction "6_6") (pintype "input"))
      (node (ref "H4") (pin "2") (pinfunction "2_2") (pintype "input"))
      (node (ref "R1") (pin "2") (pinfunction "2_2") (pintype "input"))
      (node (ref "R12") (pin "1") (pinfunction "1_1") (pintype "input"))
      (node (ref "R14") (pin "2") (pinfunction "2_2") (pintype "input"))
      (node (ref "R2") (pin "1") (pinfunction "1_1") (pintype "input"))
      (node (ref "R7") (pin "1") (pinfunction "1_1") (pintype "input"))
      (node (ref "R9") (pin "1") (pinfunction "1_1") (pintype "input"))
      (node (ref "U1") (pin "23") (pinfunction "VSS_1_23") (pintype "input"))
      (node (ref "U1") (pin "35") (pinfunction "VSS_2_35") (pintype "input"))
      (node (ref "U1") (pin "47") (pinfunction "VSS_3_47") (pintype "input"))
      (node (ref "U1") (pin "9") (pinfunction "VDDA_9") (pintype "input"))
      (node (ref "U10") (pin "2") (pinfunction "GND_2") (pintype "input"))
      (node (ref "U3") (pin "3") (pinfunction "3_3") (pintype "input"))
      (node (ref "U3") (pin "5") (pinfunction "5_5") (pintype "input"))
      (node (ref "U3") (pin "6") (pinfunction "6_6") (pintype "input"))
      (node (ref "U4") (pin "2") (pinfunction "GND_2") (pintype "input"))
      (node (ref "U4") (pin "8") (pinfunction "STB_8") (pintype "input"))
      (node (ref "U5") (pin "2") (pinfunction "GND_2") (pintype "input"))
      (node (ref "U5") (pin "5") (pinfunction "WP_5") (pintype "input"))
      (node (ref "U6") (pin "3") (pinfunction "3_3") (pintype "input"))
      (node (ref "U6") (pin "5") (pinfunction "5_5") (pintype "input"))
      (node (ref "U6") (pin "6") (pinfunction "6_6") (pintype "input"))
      (node (ref "U7") (pin "3") (pinfunction "3_3") (pintype "input"))
      (node (ref "U7") (pin "5") (pinfunction "5_5") (pintype "input"))
      (node (ref "U7") (pin "6") (pinfunction "6_6") (pintype "input"))
      (node (ref "U8") (pin "2") (pinfunction "GND_2") (pintype "input"))
      (node (ref "VCC") (pin "2") (pinfunction "C_2") (pintype "input"))
      (node (ref "VIN") (pin "2") (pinfunction "C_2") (pintype "input"))
      (node (ref "X1") (pin "2") (pinfunction "GND_2") (pintype "input"))
      (node (ref "X1") (pin "4") (pinfunction "GND_4") (pintype "input"))
    )
    (net (code "29") (name "Net-(D1-C)") (class "Default")
      (node (ref "D1") (pin "1") (pinfunction "C_1") (pintype "input"))
      (node (ref "U11") (pin "2") (pinfunction "2_2") (pintype "input"))
      (node (ref "U2") (pin "3") (pinfunction "SW_3") (pintype "input"))
      (node (ref "U2") (pin "6") (pinfunction "SW_6") (pintype "input"))
    )
    (net (code "30") (name "Net-(PC13-A)") (class "Default")
      (node (ref "PC13") (pin "1") (pinfunction "A_1") (pintype "input"))
      (node (ref "R3") (pin "1") (pinfunction "1_1") (pintype "input"))
    )
    (net (code "31") (name "Net-(R14-Pad1)") (class "Default")
      (node (ref "R14") (pin "1") (pinfunction "1_1") (pintype "input"))
      (node (ref "R4") (pin "1") (pinfunction "1_1") (pintype "input"))
    )
    (net (code "32") (name "Net-(U1-BOOT0)") (class "Default")
      (node (ref "R1") (pin "1") (pinfunction "1_1") (pintype "input"))
      (node (ref "U1") (pin "44") (pinfunction "BOOT0_44") (pintype "input"))
    )
    (net (code "33") (name "Net-(U1-PB2)") (class "Default")
      (node (ref "R2") (pin "2") (pinfunction "2_2") (pintype "input"))
      (node (ref "U1") (pin "20") (pinfunction "PB2_20") (pintype "input"))
    )
    (net (code "34") (name "Net-(U1-PC13-TAMPER-RTC)") (class "Default")
      (node (ref "R3") (pin "2") (pinfunction "2_2") (pintype "input"))
      (node (ref "U1") (pin "2") (pinfunction "PC13-TAMPER-RTC_2") (pintype "input"))
    )
    (net (code "35") (name "Net-(U2-VC)") (class "Default")
      (node (ref "C5") (pin "2") (pinfunction "2_2") (pintype "input"))
      (node (ref "U2") (pin "4") (pinfunction "VC_4") (pintype "input"))
    )
    (net (code "36") (name "Net-(U10-EN)") (class "Default")
      (node (ref "C14") (pin "2") (pinfunction "2_2") (pintype "input"))
      (node (ref "C15") (pin "2") (pinfunction "2_2") (pintype "input"))
      (node (ref "F2") (pin "2") (pinfunction "2_2") (pintype "input"))
      (node (ref "U10") (pin "1") (pinfunction "IN_1") (pintype "input"))
      (node (ref "U10") (pin "3") (pinfunction "EN_3") (pintype "input"))
    )
    (net (code "37") (name "Net-(VCC-A)") (class "Default")
      (node (ref "R15") (pin "1") (pinfunction "1_1") (pintype "input"))
      (node (ref "VCC") (pin "1") (pinfunction "A_1") (pintype "input"))
    )
    (net (code "38") (name "Net-(VIN-A)") (class "Default")
      (node (ref "R16") (pin "1") (pinfunction "1_1") (pintype "input"))
      (node (ref "VIN") (pin "1") (pinfunction "A_1") (pintype "input"))
    )
    (net (code "39") (name "VCC") (class "Default")
      (node (ref "C8") (pin "2") (pinfunction "2_2") (pintype "input"))
      (node (ref "C9") (pin "1") (pinfunction "1_1") (pintype "input"))
      (node (ref "F2") (pin "1") (pinfunction "1_1") (pintype "input"))
      (node (ref "H2") (pin "1") (pinfunction "1_1") (pintype "input"))
      (node (ref "H2") (pin "2") (pinfunction "2_2") (pintype "input"))
      (node (ref "H2") (pin "3") (pinfunction "3_3") (pintype "input"))
      (node (ref "H2") (pin "4") (pinfunction "4_4") (pintype "input"))
      (node (ref "H2") (pin "5") (pinfunction "5_5") (pintype "input"))
      (node (ref "H2") (pin "6") (pinfunction "6_6") (pintype "input"))
      (node (ref "R15") (pin "2") (pinfunction "2_2") (pintype "input"))
      (node (ref "R4") (pin "3") (pinfunction "3_3") (pintype "input"))
      (node (ref "R6") (pin "2") (pinfunction "2_2") (pintype "input"))
      (node (ref "U11") (pin "1") (pinfunction "1_1") (pintype "input"))
    )
    (net (code "40") (name "VIN") (class "Default")
      (node (ref "C5") (pin "1") (pinfunction "1_1") (pintype "input"))
      (node (ref "C6") (pin "2") (pinfunction "2_2") (pintype "input"))
      (node (ref "C7") (pin "1") (pinfunction "1_1") (pintype "input"))
      (node (ref "DC1") (pin "4") (pinfunction "4_4") (pintype "input"))
      (node (ref "R16") (pin "2") (pinfunction "2_2") (pintype "input"))
      (node (ref "R8") (pin "2") (pinfunction "2_2") (pintype "input"))
      (node (ref "U2") (pin "5") (pinfunction "VIN_5") (pintype "input"))
    )
    (net (code "41") (name "unconnected-(U1-PA0-WKUP-Pad10)") (class "Default")
      (node (ref "U1") (pin "10") (pinfunction "PA0-WKUP_10") (pintype "input+no_connect"))
    )
    (net (code "42") (name "unconnected-(U1-PA3-Pad13)") (class "Default")
      (node (ref "U1") (pin "13") (pinfunction "PA3_13") (pintype "input+no_connect"))
    )
    (net (code "43") (name "unconnected-(U1-PA4-Pad14)") (class "Default")
      (node (ref "U1") (pin "14") (pinfunction "PA4_14") (pintype "input+no_connect"))
    )
    (net (code "44") (name "unconnected-(U1-PA5-Pad15)") (class "Default")
      (node (ref "U1") (pin "15") (pinfunction "PA5_15") (pintype "input+no_connect"))
    )
    (net (code "45") (name "unconnected-(U1-PA8-Pad29)") (class "Default")
      (node (ref "U1") (pin "29") (pinfunction "PA8_29") (pintype "input+no_connect"))
    )
    (net (code "46") (name "unconnected-(U1-PA11-Pad32)") (class "Default")
      (node (ref "U1") (pin "32") (pinfunction "PA11_32") (pintype "input+no_connect"))
    )
    (net (code "47") (name "unconnected-(U1-PA12-Pad33)") (class "Default")
      (node (ref "U1") (pin "33") (pinfunction "PA12_33") (pintype "input+no_connect"))
    )
    (net (code "48") (name "unconnected-(U1-PA15-Pad38)") (class "Default")
      (node (ref "U1") (pin "38") (pinfunction "PA15_38") (pintype "input+no_connect"))
    )
    (net (code "49") (name "unconnected-(U1-PB3-Pad39)") (class "Default")
      (node (ref "U1") (pin "39") (pinfunction "PB3_39") (pintype "input+no_connect"))
    )
    (net (code "50") (name "unconnected-(U1-PB4-Pad40)") (class "Default")
      (node (ref "U1") (pin "40") (pinfunction "PB4_40") (pintype "input+no_connect"))
    )
    (net (code "51") (name "unconnected-(U1-PB5-Pad41)") (class "Default")
      (node (ref "U1") (pin "41") (pinfunction "PB5_41") (pintype "input+no_connect"))
    )
    (net (code "52") (name "unconnected-(U1-PB12-Pad25)") (class "Default")
      (node (ref "U1") (pin "25") (pinfunction "PB12_25") (pintype "input+no_connect"))
    )
    (net (code "53") (name "unconnected-(U1-PB13-Pad26)") (class "Default")
      (node (ref "U1") (pin "26") (pinfunction "PB13_26") (pintype "input+no_connect"))
    )
    (net (code "54") (name "unconnected-(U1-PB14-Pad27)") (class "Default")
      (node (ref "U1") (pin "27") (pinfunction "PB14_27") (pintype "input+no_connect"))
    )
    (net (code "55") (name "unconnected-(U1-PB15-Pad28)") (class "Default")
      (node (ref "U1") (pin "28") (pinfunction "PB15_28") (pintype "input+no_connect"))
    )
    (net (code "56") (name "unconnected-(U4-EP-Pad9)") (class "Default")
      (node (ref "U4") (pin "9") (pinfunction "EP_9") (pintype "input+no_connect"))
    )
    (net (code "57") (name "unconnected-(U8-BYP-Pad4)") (class "Default")
      (node (ref "U8") (pin "4") (pinfunction "BYP_4") (pintype "input+no_connect"))
    )
    (net (code "58") (name "unconnected-(U10-BYP-Pad4)") (class "Default")
      (node (ref "U10") (pin "4") (pinfunction "BYP_4") (pintype "input+no_connect"))
    )
  )
)
